# Microkontroller.net
KiCad netlist of a schematic drawn in EAGLE
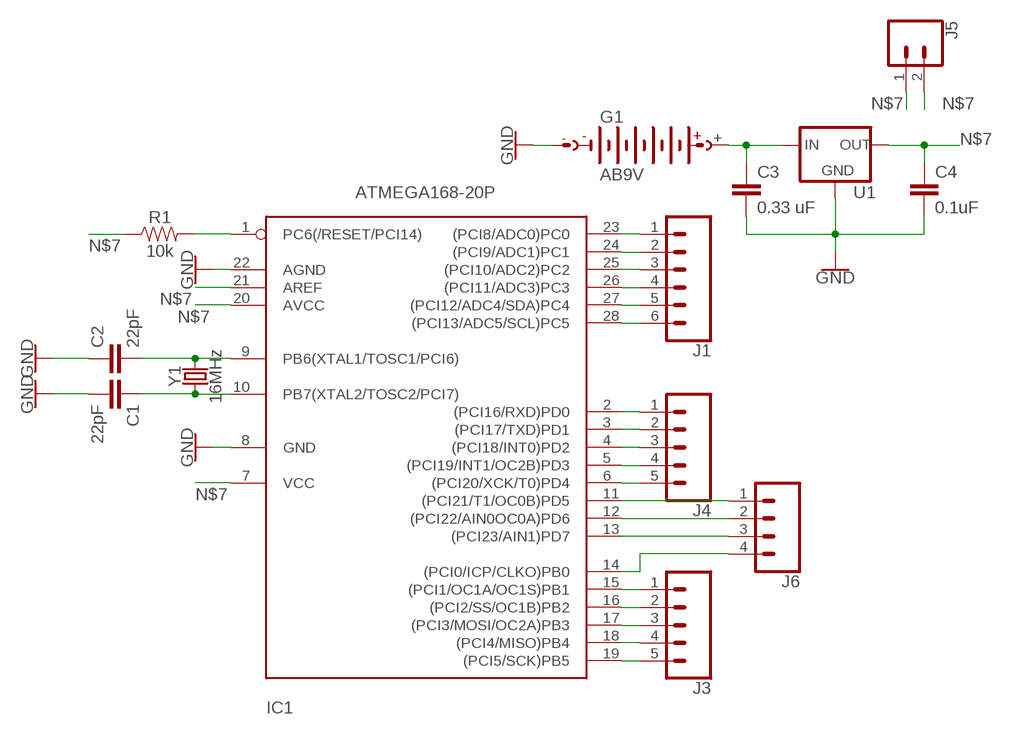
[diagram p0: schematic, sheet 1]

(export (version "E")
  (design (tool "Eeschema 10.0.6"))
  (components
    (comp (ref "C1")
      (value "22pF")
      (footprint "eagle-import:CAP-PTH-2.54")
      (libsource (lib "eagle-import") (part "22PF-PTH-2.54MM-200V-5%"))
    )
    (comp (ref "C2")
      (value "22pF")
      (footprint "eagle-import:CAP-PTH-2.54")
      (libsource (lib "eagle-import") (part "22PF-PTH-2.54MM-200V-5%"))
    )
    (comp (ref "C3")
      (value "0.33 uF")
      (footprint "eagle-import:C2.5-2")
      (libsource (lib "eagle-import") (part "C2.5/2"))
    )
    (comp (ref "C4")
      (value "0.1uF")
      (footprint "eagle-import:CAP-PTH-SMALL-KIT")
      (libsource (lib "eagle-import") (part "0.1UF-KIT-EZ-50V-20%"))
    )
    (comp (ref "G1")
      (value "AB9V")
      (footprint "eagle-import:AB9V")
      (libsource (lib "eagle-import") (part "AB9V"))
    )
    (comp (ref "IC1")
      (value "ATMEGA168-20P")
      (footprint "eagle-import:DIL28-3")
      (libsource (lib "eagle-import") (part "ATMEGA168P-20"))
    )
    (comp (ref "J1")
      (value "CONN_06SILK_FEMALE_PTH")
      (footprint "eagle-import:1X06")
      (libsource (lib "eagle-import") (part "CONN_06SILK_FEMALE_PTH"))
    )
    (comp (ref "J3")
      (value "CONN_05")
      (footprint "eagle-import:1X05")
      (libsource (lib "eagle-import") (part "CONN_05"))
    )
    (comp (ref "J4")
      (value "CONN_05")
      (footprint "eagle-import:1X05")
      (libsource (lib "eagle-import") (part "CONN_05"))
    )
    (comp (ref "J5")
      (value "CONN_02")
      (footprint "eagle-import:1X02")
      (libsource (lib "eagle-import") (part "CONN_02"))
    )
    (comp (ref "J6")
      (value "CONN_04")
      (footprint "eagle-import:1X04")
      (libsource (lib "eagle-import") (part "CONN_04"))
    )
    (comp (ref "R1")
      (value "10k")
      (footprint "eagle-import:AXIAL-0.3")
      (libsource (lib "eagle-import") (part "10KOHM-HORIZ-1/4W-1%"))
    )
    (comp (ref "U1")
      (value "V_REG_78XXSIDE")
      (footprint "eagle-import:78XXL")
      (libsource (lib "eagle-import") (part "V_REG_78XXSIDE"))
    )
    (comp (ref "Y1")
      (value "16MHz")
      (footprint "eagle-import:HC49US")
      (libsource (lib "eagle-import") (part "CRYSTAL-16MHZPTH-HC49US"))
    )
  )
  (nets
    (net (code "1") (name "/N$7") (class "Default")
      (node (ref "C4") (pin "1") (pinfunction "1_1") (pintype "passive"))
      (node (ref "IC1") (pin "20") (pinfunction "AVCC_20") (pintype "bidirectional"))
      (node (ref "IC1") (pin "21") (pinfunction "AREF_21") (pintype "bidirectional"))
      (node (ref "IC1") (pin "7") (pinfunction "VCC_7") (pintype "bidirectional"))
      (node (ref "J5") (pin "1") (pinfunction "1_1") (pintype "passive"))
      (node (ref "J5") (pin "2") (pinfunction "2_2") (pintype "passive"))
      (node (ref "R1") (pin "P$1") (pinfunction "1_P$1") (pintype "passive"))
      (node (ref "U1") (pin "OUT") (pinfunction "OUT_OUT") (pintype "passive"))
    )
    (net (code "2") (name "GND") (class "Default")
      (node (ref "C1") (pin "2") (pinfunction "2_2") (pintype "passive"))
      (node (ref "C2") (pin "1") (pinfunction "1_1") (pintype "passive"))
      (node (ref "C3") (pin "2") (pinfunction "2_2") (pintype "passive"))
      (node (ref "C4") (pin "2") (pinfunction "2_2") (pintype "passive"))
      (node (ref "G1") (pin "-") (pinfunction "-_-") (pintype "passive"))
      (node (ref "IC1") (pin "22") (pinfunction "AGND_22") (pintype "bidirectional"))
      (node (ref "IC1") (pin "8") (pinfunction "GND_8") (pintype "bidirectional"))
      (node (ref "U1") (pin "GND") (pinfunction "GND_GND") (pintype "input"))
    )
    (net (code "3") (name "Net-(C3-Pad1)") (class "Default")
      (node (ref "C3") (pin "1") (pinfunction "1_1") (pintype "passive"))
      (node (ref "G1") (pin "+") (pinfunction "+_+") (pintype "passive"))
      (node (ref "U1") (pin "IN") (pinfunction "IN_IN") (pintype "input"))
    )
    (net (code "4") (name "Net-(IC1-(PCI0{slash}ICP{slash}CLKO)PB0)") (class "Default")
      (node (ref "IC1") (pin "14") (pinfunction "(PCI0/ICP/CLKO)PB0_14") (pintype "bidirectional"))
      (node (ref "J6") (pin "4") (pinfunction "4_4") (pintype "passive"))
    )
    (net (code "5") (name "Net-(IC1-(PCI1{slash}OC1A{slash}OC1S)PB1)") (class "Default")
      (node (ref "IC1") (pin "15") (pinfunction "(PCI1/OC1A/OC1S)PB1_15") (pintype "bidirectional"))
      (node (ref "J3") (pin "1") (pinfunction "1_1") (pintype "passive"))
    )
    (net (code "6") (name "Net-(IC1-(PCI2{slash}SS{slash}OC1B)PB2)") (class "Default")
      (node (ref "IC1") (pin "16") (pinfunction "(PCI2/SS/OC1B)PB2_16") (pintype "bidirectional"))
      (node (ref "J3") (pin "2") (pinfunction "2_2") (pintype "passive"))
    )
    (net (code "7") (name "Net-(IC1-(PCI3{slash}MOSI{slash}OC2A)PB3)") (class "Default")
      (node (ref "IC1") (pin "17") (pinfunction "(PCI3/MOSI/OC2A)PB3_17") (pintype "bidirectional"))
      (node (ref "J3") (pin "3") (pinfunction "3_3") (pintype "passive"))
    )
    (net (code "8") (name "Net-(IC1-(PCI4{slash}MISO)PB4)") (class "Default")
      (node (ref "IC1") (pin "18") (pinfunction "(PCI4/MISO)PB4_18") (pintype "bidirectional"))
      (node (ref "J3") (pin "4") (pinfunction "4_4") (pintype "passive"))
    )
    (net (code "9") (name "Net-(IC1-(PCI5{slash}SCK)PB5)") (class "Default")
      (node (ref "IC1") (pin "19") (pinfunction "(PCI5/SCK)PB5_19") (pintype "bidirectional"))
      (node (ref "J3") (pin "5") (pinfunction "5_5") (pintype "passive"))
    )
    (net (code "10") (name "Net-(IC1-(PCI8{slash}ADC0)PC0)") (class "Default")
      (node (ref "IC1") (pin "23") (pinfunction "(PCI8/ADC0)PC0_23") (pintype "bidirectional"))
      (node (ref "J1") (pin "1") (pinfunction "1_1") (pintype "passive"))
    )
    (net (code "11") (name "Net-(IC1-(PCI9{slash}ADC1)PC1)") (class "Default")
      (node (ref "IC1") (pin "24") (pinfunction "(PCI9/ADC1)PC1_24") (pintype "bidirectional"))
      (node (ref "J1") (pin "2") (pinfunction "2_2") (pintype "passive"))
    )
    (net (code "12") (name "Net-(IC1-(PCI10{slash}ADC2)PC2)") (class "Default")
      (node (ref "IC1") (pin "25") (pinfunction "(PCI10/ADC2)PC2_25") (pintype "bidirectional"))
      (node (ref "J1") (pin "3") (pinfunction "3_3") (pintype "passive"))
    )
    (net (code "13") (name "Net-(IC1-(PCI11{slash}ADC3)PC3)") (class "Default")
      (node (ref "IC1") (pin "26") (pinfunction "(PCI11/ADC3)PC3_26") (pintype "bidirectional"))
      (node (ref "J1") (pin "4") (pinfunction "4_4") (pintype "passive"))
    )
    (net (code "14") (name "Net-(IC1-(PCI12{slash}ADC4{slash}SDA)PC4)") (class "Default")
      (node (ref "IC1") (pin "27") (pinfunction "(PCI12/ADC4/SDA)PC4_27") (pintype "bidirectional"))
      (node (ref "J1") (pin "5") (pinfunction "5_5") (pintype "passive"))
    )
    (net (code "15") (name "Net-(IC1-(PCI13{slash}ADC5{slash}SCL)PC5)") (class "Default")
      (node (ref "IC1") (pin "28") (pinfunction "(PCI13/ADC5/SCL)PC5_28") (pintype "bidirectional"))
      (node (ref "J1") (pin "6") (pinfunction "6_6") (pintype "passive"))
    )
    (net (code "16") (name "Net-(IC1-(PCI16{slash}RXD)PD0)") (class "Default")
      (node (ref "IC1") (pin "2") (pinfunction "(PCI16/RXD)PD0_2") (pintype "bidirectional"))
      (node (ref "J4") (pin "1") (pinfunction "1_1") (pintype "passive"))
    )
    (net (code "17") (name "Net-(IC1-(PCI17{slash}TXD)PD1)") (class "Default")
      (node (ref "IC1") (pin "3") (pinfunction "(PCI17/TXD)PD1_3") (pintype "bidirectional"))
      (node (ref "J4") (pin "2") (pinfunction "2_2") (pintype "passive"))
    )
    (net (code "18") (name "Net-(IC1-(PCI18{slash}INT0)PD2)") (class "Default")
      (node (ref "IC1") (pin "4") (pinfunction "(PCI18/INT0)PD2_4") (pintype "bidirectional"))
      (node (ref "J4") (pin "3") (pinfunction "3_3") (pintype "passive"))
    )
    (net (code "19") (name "Net-(IC1-(PCI19{slash}INT1{slash}OC2B)PD3)") (class "Default")
      (node (ref "IC1") (pin "5") (pinfunction "(PCI19/INT1/OC2B)PD3_5") (pintype "bidirectional"))
      (node (ref "J4") (pin "4") (pinfunction "4_4") (pintype "passive"))
    )
    (net (code "20") (name "Net-(IC1-(PCI20{slash}XCK{slash}T0)PD4)") (class "Default")
      (node (ref "IC1") (pin "6") (pinfunction "(PCI20/XCK/T0)PD4_6") (pintype "bidirectional"))
      (node (ref "J4") (pin "5") (pinfunction "5_5") (pintype "passive"))
    )
    (net (code "21") (name "Net-(IC1-(PCI21{slash}T1{slash}OC0B)PD5)") (class "Default")
      (node (ref "IC1") (pin "11") (pinfunction "(PCI21/T1/OC0B)PD5_11") (pintype "bidirectional"))
      (node (ref "J6") (pin "1") (pinfunction "1_1") (pintype "passive"))
    )
    (net (code "22") (name "Net-(IC1-(PCI22{slash}AIN0OC0A)PD6)") (class "Default")
      (node (ref "IC1") (pin "12") (pinfunction "(PCI22/AIN0OC0A)PD6_12") (pintype "bidirectional"))
      (node (ref "J6") (pin "2") (pinfunction "2_2") (pintype "passive"))
    )
    (net (code "23") (name "Net-(IC1-(PCI23{slash}AIN1)PD7)") (class "Default")
      (node (ref "IC1") (pin "13") (pinfunction "(PCI23/AIN1)PD7_13") (pintype "bidirectional"))
      (node (ref "J6") (pin "3") (pinfunction "3_3") (pintype "passive"))
    )
    (net (code "24") (name "Net-(IC1-PB6(XTAL1{slash}TOSC1{slash}PCI6))") (class "Default")
      (node (ref "C2") (pin "2") (pinfunction "2_2") (pintype "passive"))
      (node (ref "IC1") (pin "9") (pinfunction "PB6(XTAL1/TOSC1/PCI6)_9") (pintype "bidirectional"))
      (node (ref "Y1") (pin "2") (pinfunction "2_2") (pintype "passive"))
    )
    (net (code "25") (name "Net-(IC1-PB7(XTAL2{slash}TOSC2{slash}PCI7))") (class "Default")
      (node (ref "C1") (pin "1") (pinfunction "1_1") (pintype "passive"))
      (node (ref "IC1") (pin "10") (pinfunction "PB7(XTAL2/TOSC2/PCI7)_10") (pintype "bidirectional"))
      (node (ref "Y1") (pin "1") (pinfunction "1_1") (pintype "passive"))
    )
    (net (code "26") (name "Net-(IC1-PC6({slash}RESET{slash}PCI14))") (class "Default")
      (node (ref "IC1") (pin "1") (pinfunction "PC6(/RESET/PCI14)_1") (pintype "bidirectional"))
      (node (ref "R1") (pin "P$2") (pinfunction "2_P$2") (pintype "passive"))
    )
  )
)
